# Mind-Synchronizing-Generator-PinHdrPotX-.net
KiCad netlist of a schematic drawn in EAGLE
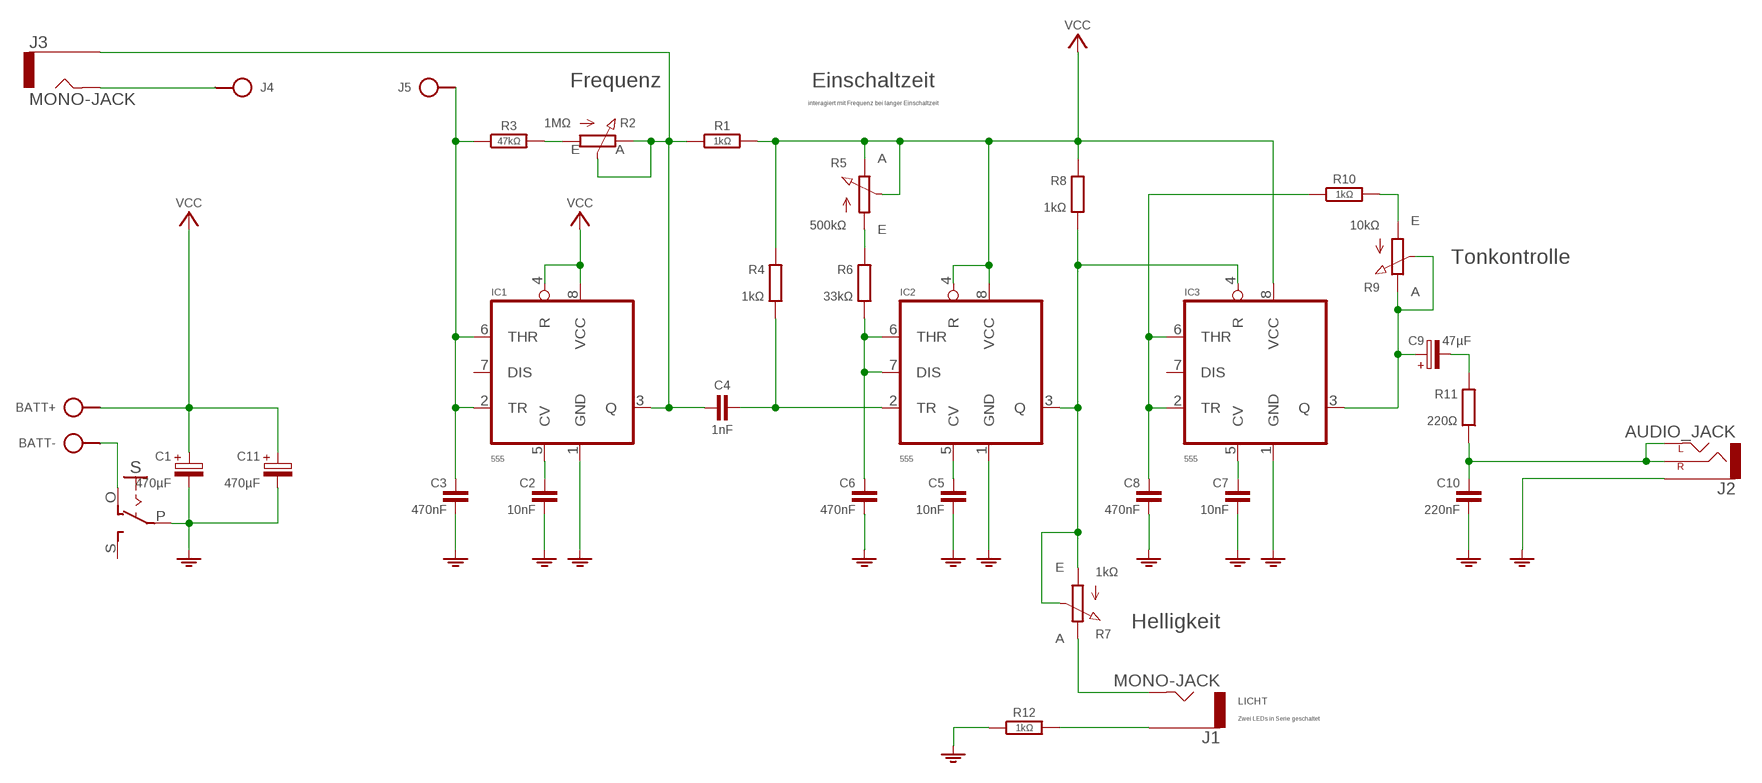
[diagram p0: schematic, sheet 1]

(export (version "E")
  (design (tool "Eeschema 10.0.6"))
  (components
    (comp (ref "BATT")
      (value "SPAD+--+")
      (footprint "eagle-import:SPAD-+")
      (libsource (lib "eagle-import") (part "SPAD+--+"))
    )
    (comp (ref "C1")
      (value "470µF")
      (footprint "eagle-import:E2,5-6")
      (libsource (lib "eagle-import") (part "CPOLE2.5-6"))
    )
    (comp (ref "C2")
      (value "10nF")
      (footprint "eagle-import:C050-020X044")
      (libsource (lib "eagle-import") (part "C050-020X044"))
    )
    (comp (ref "C3")
      (value "470nF")
      (footprint "eagle-import:C050-040X075")
      (libsource (lib "eagle-import") (part "C050-040X075"))
    )
    (comp (ref "C4")
      (value "1nF")
      (footprint "eagle-import:C050-020X044")
      (libsource (lib "eagle-import") (part "C-H050-020X044"))
    )
    (comp (ref "C5")
      (value "10nF")
      (footprint "eagle-import:C050-020X044_V")
      (libsource (lib "eagle-import") (part "C050-020X044/V"))
    )
    (comp (ref "C6")
      (value "470nF")
      (footprint "eagle-import:C050-040X075")
      (libsource (lib "eagle-import") (part "C050-040X075"))
    )
    (comp (ref "C7")
      (value "10nF")
      (footprint "eagle-import:C075-020X044_V")
      (libsource (lib "eagle-import") (part "C075-020X044/V"))
    )
    (comp (ref "C8")
      (value "470nF")
      (footprint "eagle-import:C050-040X075")
      (libsource (lib "eagle-import") (part "C050-040X075"))
    )
    (comp (ref "C9")
      (value "47µF")
      (footprint "eagle-import:E2,5-4")
      (libsource (lib "eagle-import") (part "CPOL-HE2,5-4"))
    )
    (comp (ref "C10")
      (value "220nF")
      (footprint "eagle-import:C050-025X060")
      (libsource (lib "eagle-import") (part "C025-025X060"))
    )
    (comp (ref "C11")
      (value "470µF")
      (footprint "eagle-import:E2,5-6")
      (libsource (lib "eagle-import") (part "CPOLE2.5-6"))
    )
    (comp (ref "IC1")
      (value "555")
      (footprint "eagle-import:555-DIL")
      (libsource (lib "eagle-import") (part "555_ALT2-LBL"))
    )
    (comp (ref "IC2")
      (value "555")
      (footprint "eagle-import:555-DIL")
      (libsource (lib "eagle-import") (part "555_ALT2-LBL"))
    )
    (comp (ref "IC3")
      (value "555")
      (footprint "eagle-import:555-DIL")
      (libsource (lib "eagle-import") (part "555_ALT2-LBL"))
    )
    (comp (ref "J1")
      (value "MONO-JACK")
      (footprint "eagle-import:STEREOJACK2.5MM_STEREOJACK2.5MM")
      (libsource (lib "eagle-import") (part "MONO-JACK"))
    )
    (comp (ref "J2")
      (value "AUDIO_JACK")
      (footprint "eagle-import:AUDIO-JACK")
      (libsource (lib "eagle-import") (part "AUDIO_JACK"))
    )
    (comp (ref "J3")
      (value "MONO-JACK")
      (footprint "eagle-import:STEREOJACK2.5MM_STEREOJACK2.5MM")
      (libsource (lib "eagle-import") (part "MONO-JACK"))
    )
    (comp (ref "J4")
      (value "HPORT")
      (footprint "eagle-import:SPAD")
      (libsource (lib "eagle-import") (part "HPORT"))
    )
    (comp (ref "J5")
      (value "HPORT")
      (footprint "eagle-import:SPAD")
      (libsource (lib "eagle-import") (part "HPORT"))
    )
    (comp (ref "R1")
      (value "1kΩ")
      (footprint "eagle-import:0204_10")
      (libsource (lib "eagle-import") (part "R-H0204/10"))
    )
    (comp (ref "R2")
      (value "1MΩ")
      (footprint "eagle-import:CONN-3P")
      (libsource (lib "eagle-import") (part "POT-H-3P"))
    )
    (comp (ref "R3")
      (value "47kΩ")
      (footprint "eagle-import:0204_10")
      (libsource (lib "eagle-import") (part "R-H0204/10"))
    )
    (comp (ref "R4")
      (value "1kΩ")
      (footprint "eagle-import:0204_10-V")
      (libsource (lib "eagle-import") (part "R0204/10-V"))
    )
    (comp (ref "R5")
      (value "500kΩ")
      (footprint "eagle-import:CONN-3P")
      (libsource (lib "eagle-import") (part "POT-3P"))
    )
    (comp (ref "R6")
      (value "33kΩ")
      (footprint "eagle-import:0204_10")
      (libsource (lib "eagle-import") (part "R0204/10"))
    )
    (comp (ref "R7")
      (value "1kΩ")
      (footprint "eagle-import:CONN-3P")
      (libsource (lib "eagle-import") (part "POT-3P-S1"))
    )
    (comp (ref "R8")
      (value "1kΩ")
      (footprint "eagle-import:0204_10-V")
      (libsource (lib "eagle-import") (part "R0204/10-V"))
    )
    (comp (ref "R9")
      (value "10kΩ")
      (footprint "eagle-import:CONN-3P")
      (libsource (lib "eagle-import") (part "POT-3P"))
    )
    (comp (ref "R10")
      (value "1kΩ")
      (footprint "eagle-import:0204_10")
      (libsource (lib "eagle-import") (part "R-H0204/10"))
    )
    (comp (ref "R11")
      (value "220Ω")
      (footprint "eagle-import:0204_10-V")
      (libsource (lib "eagle-import") (part "R0204/10-V"))
    )
    (comp (ref "R12")
      (value "1kΩ")
      (footprint "eagle-import:0204_10")
      (libsource (lib "eagle-import") (part "R-H0204/10"))
    )
    (comp (ref "S")
      (value "SL-SW-1P-2T-H")
      (footprint "eagle-import:SLSW-1P2T-H")
      (libsource (lib "eagle-import") (part "SL-SW-1P-2T-H"))
    )
  )
  (nets
    (net (code "1") (name "GND") (class "Default")
      (node (ref "C1") (pin "-") (pinfunction "-_-") (pintype "passive"))
      (node (ref "C10") (pin "2") (pinfunction "2_2") (pintype "passive"))
      (node (ref "C11") (pin "-") (pinfunction "-_-") (pintype "passive"))
      (node (ref "C2") (pin "2") (pinfunction "2_2") (pintype "passive"))
      (node (ref "C3") (pin "2") (pinfunction "2_2") (pintype "passive"))
      (node (ref "C5") (pin "2") (pinfunction "2_2") (pintype "passive"))
      (node (ref "C6") (pin "2") (pinfunction "2_2") (pintype "passive"))
      (node (ref "C7") (pin "2") (pinfunction "2_2") (pintype "passive"))
      (node (ref "C8") (pin "2") (pinfunction "2_2") (pintype "passive"))
      (node (ref "IC1") (pin "1") (pinfunction "GND_1") (pintype "power_in"))
      (node (ref "IC2") (pin "1") (pinfunction "GND_1") (pintype "power_in"))
      (node (ref "IC3") (pin "1") (pinfunction "GND_1") (pintype "power_in"))
      (node (ref "J2") (pin "SLEEVE") (pinfunction "SLEEVE_SLEEVE") (pintype "bidirectional"))
      (node (ref "R12") (pin "1") (pinfunction "1_1") (pintype "passive"))
      (node (ref "S") (pin "P") (pinfunction "P_P") (pintype "passive"))
    )
    (net (code "2") (name "Net-(BATTB-P$1)") (class "Default")
      (node (ref "BATT") (pin "1") (pinfunction "P$1_1") (pintype "passive"))
      (node (ref "S") (pin "O") (pinfunction "O_O") (pintype "passive"))
    )
    (net (code "3") (name "Net-(IC1-CV)") (class "Default")
      (node (ref "C2") (pin "1") (pinfunction "1_1") (pintype "passive"))
      (node (ref "IC1") (pin "5") (pinfunction "CV_5") (pintype "input"))
    )
    (net (code "4") (name "Net-(IC1-Q)") (class "Default")
      (node (ref "C4") (pin "1") (pinfunction "1_1") (pintype "passive"))
      (node (ref "IC1") (pin "3") (pinfunction "Q_3") (pintype "output"))
      (node (ref "J3") (pin "SHIELD") (pinfunction "SLEEVE_SHIELD") (pintype "bidirectional"))
      (node (ref "R1") (pin "1") (pinfunction "1_1") (pintype "passive"))
      (node (ref "R2") (pin "2") (pinfunction "S_2") (pintype "passive"))
      (node (ref "R2") (pin "3") (pinfunction "E_3") (pintype "passive"))
    )
    (net (code "5") (name "Net-(IC1-THR)") (class "Default")
      (node (ref "C3") (pin "1") (pinfunction "1_1") (pintype "passive"))
      (node (ref "IC1") (pin "2") (pinfunction "TR_2") (pintype "input"))
      (node (ref "IC1") (pin "6") (pinfunction "THR_6") (pintype "input"))
      (node (ref "J5") (pin "1") (pinfunction "P$1_1") (pintype "passive"))
      (node (ref "R3") (pin "1") (pinfunction "1_1") (pintype "passive"))
    )
    (net (code "6") (name "Net-(IC2-CV)") (class "Default")
      (node (ref "C5") (pin "1") (pinfunction "1_1") (pintype "passive"))
      (node (ref "IC2") (pin "5") (pinfunction "CV_5") (pintype "input"))
    )
    (net (code "7") (name "Net-(IC2-DIS)") (class "Default")
      (node (ref "C6") (pin "1") (pinfunction "1_1") (pintype "passive"))
      (node (ref "IC2") (pin "6") (pinfunction "THR_6") (pintype "input"))
      (node (ref "IC2") (pin "7") (pinfunction "DIS_7") (pintype "passive"))
      (node (ref "R6") (pin "2") (pinfunction "1_2") (pintype "passive"))
    )
    (net (code "8") (name "Net-(IC2-Q)") (class "Default")
      (node (ref "IC2") (pin "3") (pinfunction "Q_3") (pintype "output"))
      (node (ref "IC3") (pin "4") (pinfunction "R_4") (pintype "input"))
      (node (ref "R7") (pin "1") (pinfunction "S_1") (pintype "passive"))
      (node (ref "R7") (pin "2") (pinfunction "A_2") (pintype "passive"))
      (node (ref "R8") (pin "2") (pinfunction "1_2") (pintype "passive"))
    )
    (net (code "9") (name "Net-(IC2-TR)") (class "Default")
      (node (ref "C4") (pin "2") (pinfunction "2_2") (pintype "passive"))
      (node (ref "IC2") (pin "2") (pinfunction "TR_2") (pintype "input"))
      (node (ref "R4") (pin "2") (pinfunction "1_2") (pintype "passive"))
    )
    (net (code "10") (name "Net-(IC3-CV)") (class "Default")
      (node (ref "C7") (pin "1") (pinfunction "1_1") (pintype "passive"))
      (node (ref "IC3") (pin "5") (pinfunction "CV_5") (pintype "input"))
    )
    (net (code "11") (name "Net-(IC3-Q)") (class "Default")
      (node (ref "C9") (pin "+") (pinfunction "+_+") (pintype "passive"))
      (node (ref "IC3") (pin "3") (pinfunction "Q_3") (pintype "output"))
      (node (ref "R9") (pin "2") (pinfunction "S_2") (pintype "passive"))
      (node (ref "R9") (pin "3") (pinfunction "E_3") (pintype "passive"))
    )
    (net (code "12") (name "Net-(IC3-THR)") (class "Default")
      (node (ref "C8") (pin "1") (pinfunction "1_1") (pintype "passive"))
      (node (ref "IC3") (pin "2") (pinfunction "TR_2") (pintype "input"))
      (node (ref "IC3") (pin "6") (pinfunction "THR_6") (pintype "input"))
      (node (ref "R10") (pin "1") (pinfunction "1_1") (pintype "passive"))
    )
    (net (code "13") (name "Net-(J1-LEFT)") (class "Default")
      (node (ref "J1") (pin "TIP") (pinfunction "LEFT_TIP") (pintype "bidirectional"))
      (node (ref "R7") (pin "3") (pinfunction "E_3") (pintype "passive"))
    )
    (net (code "14") (name "Net-(J1-SLEEVE)") (class "Default")
      (node (ref "J1") (pin "SHIELD") (pinfunction "SLEEVE_SHIELD") (pintype "bidirectional"))
      (node (ref "R12") (pin "2") (pinfunction "2_2") (pintype "passive"))
    )
    (net (code "15") (name "Net-(J2-LEFT)") (class "Default")
      (node (ref "C10") (pin "1") (pinfunction "1_1") (pintype "passive"))
      (node (ref "J2") (pin "RING") (pinfunction "RIGHT_RING") (pintype "bidirectional"))
      (node (ref "J2") (pin "TIP") (pinfunction "LEFT_TIP") (pintype "bidirectional"))
      (node (ref "R11") (pin "2") (pinfunction "1_2") (pintype "passive"))
    )
    (net (code "16") (name "Net-(J3-LEFT)") (class "Default")
      (node (ref "J3") (pin "TIP") (pinfunction "LEFT_TIP") (pintype "bidirectional"))
      (node (ref "J4") (pin "1") (pinfunction "P$1_1") (pintype "passive"))
    )
    (net (code "17") (name "Net-(R2-A)") (class "Default")
      (node (ref "R2") (pin "1") (pinfunction "A_1") (pintype "passive"))
      (node (ref "R3") (pin "2") (pinfunction "2_2") (pintype "passive"))
    )
    (net (code "18") (name "Net-(R5-A)") (class "Default")
      (node (ref "R5") (pin "1") (pinfunction "A_1") (pintype "passive"))
      (node (ref "R6") (pin "1") (pinfunction "2_1") (pintype "passive"))
    )
    (net (code "19") (name "Net-(R9-A)") (class "Default")
      (node (ref "R10") (pin "2") (pinfunction "2_2") (pintype "passive"))
      (node (ref "R9") (pin "1") (pinfunction "A_1") (pintype "passive"))
    )
    (net (code "20") (name "Net-(R11-2)") (class "Default")
      (node (ref "C9") (pin "-") (pinfunction "-_-") (pintype "passive"))
      (node (ref "R11") (pin "1") (pinfunction "2_1") (pintype "passive"))
    )
    (net (code "21") (name "VCC") (class "Default")
      (node (ref "BATT") (pin "2") (pinfunction "P$1_2") (pintype "passive"))
      (node (ref "C1") (pin "+") (pinfunction "+_+") (pintype "passive"))
      (node (ref "C11") (pin "+") (pinfunction "+_+") (pintype "passive"))
      (node (ref "IC1") (pin "4") (pinfunction "R_4") (pintype "input"))
      (node (ref "IC1") (pin "8") (pinfunction "VCC_8") (pintype "power_in"))
      (node (ref "IC2") (pin "4") (pinfunction "R_4") (pintype "input"))
      (node (ref "IC2") (pin "8") (pinfunction "VCC_8") (pintype "power_in"))
      (node (ref "IC3") (pin "8") (pinfunction "VCC_8") (pintype "power_in"))
      (node (ref "R1") (pin "2") (pinfunction "2_2") (pintype "passive"))
      (node (ref "R4") (pin "1") (pinfunction "2_1") (pintype "passive"))
      (node (ref "R5") (pin "2") (pinfunction "S_2") (pintype "passive"))
      (node (ref "R5") (pin "3") (pinfunction "E_3") (pintype "passive"))
      (node (ref "R8") (pin "1") (pinfunction "2_1") (pintype "passive"))
    )
    (net (code "22") (name "unconnected-(IC1-DIS-Pad7)") (class "Default")
      (node (ref "IC1") (pin "7") (pinfunction "DIS_7") (pintype "passive"))
    )
    (net (code "23") (name "unconnected-(IC3-DIS-Pad7)") (class "Default")
      (node (ref "IC3") (pin "7") (pinfunction "DIS_7") (pintype "passive"))
    )
    (net (code "24") (name "unconnected-(S-PadS)") (class "Default")
      (node (ref "S") (pin "S") (pinfunction "S_S") (pintype "passive"))
    )
  )
)
